# seven_segment_driver_sche2.net
KiCad netlist of a schematic drawn in Altium Designer
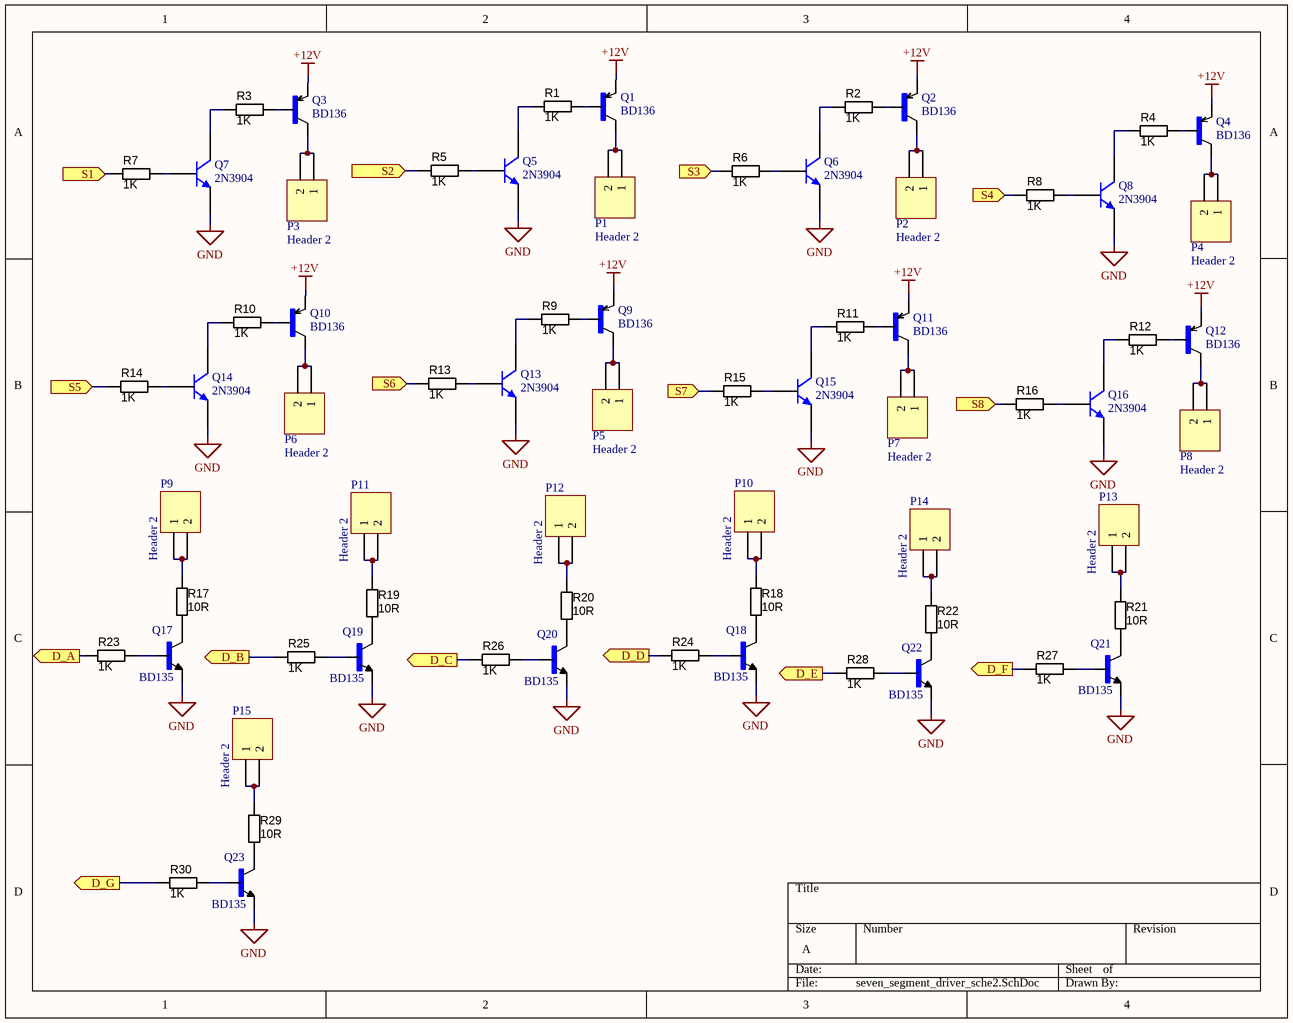
[diagram p0: seven_segment_driver_sche2.SchDoc]

(export (version "E")
  (design (tool "Eeschema 10.0.6"))
  (components
    (comp (ref "P1")
      (value "Header 2")
      (footprint "HDR1X2")
      (description "Header, 2-Pin")
      (fields (field (name "PUBLISHER") "Altium Limited"))
      (libsource (lib "Miscellaneous Connectors") (part "Header 2"))
    )
    (comp (ref "P2")
      (value "Header 2")
      (footprint "HDR1X2")
      (description "Header, 2-Pin")
      (fields (field (name "PUBLISHER") "Altium Limited"))
      (libsource (lib "Miscellaneous Connectors") (part "Header 2"))
    )
    (comp (ref "P3")
      (value "Header 2")
      (footprint "HDR1X2")
      (description "Header, 2-Pin")
      (fields (field (name "PUBLISHER") "Altium Limited"))
      (libsource (lib "Miscellaneous Connectors") (part "Header 2"))
    )
    (comp (ref "P4")
      (value "Header 2")
      (footprint "HDR1X2")
      (description "Header, 2-Pin")
      (fields (field (name "PUBLISHER") "Altium Limited"))
      (libsource (lib "Miscellaneous Connectors") (part "Header 2"))
    )
    (comp (ref "P5")
      (value "Header 2")
      (footprint "HDR1X2")
      (description "Header, 2-Pin")
      (fields (field (name "PUBLISHER") "Altium Limited"))
      (libsource (lib "Miscellaneous Connectors") (part "Header 2"))
    )
    (comp (ref "P6")
      (value "Header 2")
      (footprint "HDR1X2")
      (description "Header, 2-Pin")
      (fields (field (name "PUBLISHER") "Altium Limited"))
      (libsource (lib "Miscellaneous Connectors") (part "Header 2"))
    )
    (comp (ref "P7")
      (value "Header 2")
      (footprint "HDR1X2")
      (description "Header, 2-Pin")
      (fields (field (name "PUBLISHER") "Altium Limited"))
      (libsource (lib "Miscellaneous Connectors") (part "Header 2"))
    )
    (comp (ref "P8")
      (value "Header 2")
      (footprint "HDR1X2")
      (description "Header, 2-Pin")
      (fields (field (name "PUBLISHER") "Altium Limited"))
      (libsource (lib "Miscellaneous Connectors") (part "Header 2"))
    )
    (comp (ref "P9")
      (value "Header 2")
      (footprint "HDR1X2")
      (description "Header, 2-Pin")
      (fields (field (name "PUBLISHER") "Altium Limited"))
      (libsource (lib "") (part "Header 2_1"))
    )
    (comp (ref "P10")
      (value "Header 2")
      (footprint "HDR1X2")
      (description "Header, 2-Pin")
      (fields (field (name "PUBLISHER") "Altium Limited"))
      (libsource (lib "") (part "Header 2_1"))
    )
    (comp (ref "P11")
      (value "Header 2")
      (footprint "HDR1X2")
      (description "Header, 2-Pin")
      (fields (field (name "PUBLISHER") "Altium Limited"))
      (libsource (lib "") (part "Header 2_1"))
    )
    (comp (ref "P12")
      (value "Header 2")
      (footprint "HDR1X2")
      (description "Header, 2-Pin")
      (fields (field (name "PUBLISHER") "Altium Limited"))
      (libsource (lib "") (part "Header 2_1"))
    )
    (comp (ref "P13")
      (value "Header 2")
      (footprint "HDR1X2")
      (description "Header, 2-Pin")
      (fields (field (name "PUBLISHER") "Altium Limited"))
      (libsource (lib "") (part "Header 2_1"))
    )
    (comp (ref "P14")
      (value "Header 2")
      (footprint "HDR1X2")
      (description "Header, 2-Pin")
      (fields (field (name "PUBLISHER") "Altium Limited"))
      (libsource (lib "") (part "Header 2_1"))
    )
    (comp (ref "P15")
      (value "Header 2")
      (footprint "HDR1X2")
      (description "Header, 2-Pin")
      (fields (field (name "PUBLISHER") "Altium Limited"))
      (libsource (lib "") (part "Header 2_1"))
    )
    (comp (ref "Q1")
      (value "BD136")
      (footprint "*TO229P780X300X2000-3")
      (libsource (lib "") (part "BD136_1"))
    )
    (comp (ref "Q2")
      (value "BD136")
      (footprint "*TO229P780X300X2000-3")
      (libsource (lib "BD136") (part "BD136"))
    )
    (comp (ref "Q3")
      (value "BD136")
      (footprint "*TO229P780X300X2000-3")
      (libsource (lib "BD136") (part "BD136"))
    )
    (comp (ref "Q4")
      (value "BD136")
      (footprint "*TO229P780X300X2000-3")
      (libsource (lib "BD136") (part "BD136"))
    )
    (comp (ref "Q5")
      (value "2N3904")
      (footprint "TO-92_Flat")
      (description "NPN General Purpose Amplifier")
      (fields (field (name "PUBLISHER") "Altium Limited"))
      (libsource (lib "Miscellaneous Devices") (part "2N3904"))
    )
    (comp (ref "Q6")
      (value "2N3904")
      (footprint "TO-92_Flat")
      (description "NPN General Purpose Amplifier")
      (fields (field (name "PUBLISHER") "Altium Limited"))
      (libsource (lib "Miscellaneous Devices") (part "2N3904"))
    )
    (comp (ref "Q7")
      (value "2N3904")
      (footprint "TO-92_Flat")
      (description "NPN General Purpose Amplifier")
      (fields (field (name "PUBLISHER") "Altium Limited"))
      (libsource (lib "Miscellaneous Devices") (part "2N3904"))
    )
    (comp (ref "Q8")
      (value "2N3904")
      (footprint "TO-92_Flat")
      (description "NPN General Purpose Amplifier")
      (fields (field (name "PUBLISHER") "Altium Limited"))
      (libsource (lib "Miscellaneous Devices") (part "2N3904"))
    )
    (comp (ref "Q9")
      (value "BD136")
      (footprint "*TO229P780X300X2000-3")
      (libsource (lib "BD136") (part "BD136"))
    )
    (comp (ref "Q10")
      (value "BD136")
      (footprint "*TO229P780X300X2000-3")
      (libsource (lib "") (part "BD136_1"))
    )
    (comp (ref "Q11")
      (value "BD136")
      (footprint "*TO229P780X300X2000-3")
      (libsource (lib "BD136") (part "BD136"))
    )
    (comp (ref "Q12")
      (value "BD136")
      (footprint "*TO229P780X300X2000-3")
      (libsource (lib "BD136") (part "BD136"))
    )
    (comp (ref "Q13")
      (value "2N3904")
      (footprint "TO-92_Flat")
      (description "NPN General Purpose Amplifier")
      (fields (field (name "PUBLISHER") "Altium Limited"))
      (libsource (lib "Miscellaneous Devices") (part "2N3904"))
    )
    (comp (ref "Q14")
      (value "2N3904")
      (footprint "TO-92_Flat")
      (description "NPN General Purpose Amplifier")
      (fields (field (name "PUBLISHER") "Altium Limited"))
      (libsource (lib "Miscellaneous Devices") (part "2N3904"))
    )
    (comp (ref "Q15")
      (value "2N3904")
      (footprint "TO-92_Flat")
      (description "NPN General Purpose Amplifier")
      (fields (field (name "PUBLISHER") "Altium Limited"))
      (libsource (lib "Miscellaneous Devices") (part "2N3904"))
    )
    (comp (ref "Q16")
      (value "2N3904")
      (footprint "TO-92_Flat")
      (description "NPN General Purpose Amplifier")
      (fields (field (name "PUBLISHER") "Altium Limited"))
      (libsource (lib "Miscellaneous Devices") (part "2N3904"))
    )
    (comp (ref "Q17")
      (value "BD135")
      (footprint "*TO229P780X300X2000-3")
      (description "Trans GP BJT NPN 45V 1.5A 3-Pin TO-126")
      (fields (field (name "MF") "ON Semiconductor"))
      (libsource (lib "BD135") (part "BD135"))
    )
    (comp (ref "Q18")
      (value "BD135")
      (footprint "*TO229P780X300X2000-3")
      (description "Trans GP BJT NPN 45V 1.5A 3-Pin TO-126")
      (fields (field (name "MF") "ON Semiconductor"))
      (libsource (lib "BD135") (part "BD135"))
    )
    (comp (ref "Q19")
      (value "BD135")
      (footprint "*TO229P780X300X2000-3")
      (description "Trans GP BJT NPN 45V 1.5A 3-Pin TO-126")
      (fields (field (name "MF") "ON Semiconductor"))
      (libsource (lib "BD135") (part "BD135"))
    )
    (comp (ref "Q20")
      (value "BD135")
      (footprint "*TO229P780X300X2000-3")
      (description "Trans GP BJT NPN 45V 1.5A 3-Pin TO-126")
      (fields (field (name "MF") "ON Semiconductor"))
      (libsource (lib "BD135") (part "BD135"))
    )
    (comp (ref "Q21")
      (value "BD135")
      (footprint "*TO229P780X300X2000-3")
      (description "Trans GP BJT NPN 45V 1.5A 3-Pin TO-126")
      (fields (field (name "MF") "ON Semiconductor"))
      (libsource (lib "BD135") (part "BD135"))
    )
    (comp (ref "Q22")
      (value "BD135")
      (footprint "*TO229P780X300X2000-3")
      (description "Trans GP BJT NPN 45V 1.5A 3-Pin TO-126")
      (fields (field (name "MF") "ON Semiconductor"))
      (libsource (lib "BD135") (part "BD135"))
    )
    (comp (ref "Q23")
      (value "BD135")
      (footprint "*TO229P780X300X2000-3")
      (description "Trans GP BJT NPN 45V 1.5A 3-Pin TO-126")
      (fields (field (name "MF") "ON Semiconductor"))
      (libsource (lib "BD135") (part "BD135"))
    )
    (comp (ref "R1")
      (value "1K")
      (footprint "RESTH_AXIAL-0.4")
      (description "Resistor THD Axial 1k Ohm 0.25W 5% Carbon Film")
      (fields (field (name "TOLERANCE") "±5%") (field (name "Comment") "Carbon Film"))
      (libsource (lib "PBL - Resistors") (part "RES_1K_Axial_0.25W_5%"))
    )
    (comp (ref "R2")
      (value "1K")
      (footprint "RESTH_AXIAL-0.4")
      (description "Resistor THD Axial 1k Ohm 0.25W 5% Carbon Film")
      (fields (field (name "TOLERANCE") "±5%") (field (name "Comment") "Carbon Film"))
      (libsource (lib "PBL - Resistors") (part "RES_1K_Axial_0.25W_5%"))
    )
    (comp (ref "R3")
      (value "1K")
      (footprint "RESTH_AXIAL-0.4")
      (description "Resistor THD Axial 1k Ohm 0.25W 5% Carbon Film")
      (fields (field (name "TOLERANCE") "±5%") (field (name "Comment") "Carbon Film"))
      (libsource (lib "PBL - Resistors") (part "RES_1K_Axial_0.25W_5%"))
    )
    (comp (ref "R4")
      (value "1K")
      (footprint "RESTH_AXIAL-0.4")
      (description "Resistor THD Axial 1k Ohm 0.25W 5% Carbon Film")
      (fields (field (name "TOLERANCE") "±5%") (field (name "Comment") "Carbon Film"))
      (libsource (lib "PBL - Resistors") (part "RES_1K_Axial_0.25W_5%"))
    )
    (comp (ref "R5")
      (value "1K")
      (footprint "RESTH_AXIAL-0.4")
      (description "Resistor THD Axial 1k Ohm 0.25W 5% Carbon Film")
      (fields (field (name "TOLERANCE") "±5%") (field (name "Comment") "Carbon Film"))
      (libsource (lib "PBL - Resistors") (part "RES_1K_Axial_0.25W_5%"))
    )
    (comp (ref "R6")
      (value "1K")
      (footprint "RESTH_AXIAL-0.4")
      (description "Resistor THD Axial 1k Ohm 0.25W 5% Carbon Film")
      (fields (field (name "TOLERANCE") "±5%") (field (name "Comment") "Carbon Film"))
      (libsource (lib "PBL - Resistors") (part "RES_1K_Axial_0.25W_5%"))
    )
    (comp (ref "R7")
      (value "1K")
      (footprint "RESTH_AXIAL-0.4")
      (description "Resistor THD Axial 1k Ohm 0.25W 5% Carbon Film")
      (fields (field (name "TOLERANCE") "±5%") (field (name "Comment") "Carbon Film"))
      (libsource (lib "PBL - Resistors") (part "RES_1K_Axial_0.25W_5%"))
    )
    (comp (ref "R8")
      (value "1K")
      (footprint "RESTH_AXIAL-0.4")
      (description "Resistor THD Axial 1k Ohm 0.25W 5% Carbon Film")
      (fields (field (name "TOLERANCE") "±5%") (field (name "Comment") "Carbon Film"))
      (libsource (lib "PBL - Resistors") (part "RES_1K_Axial_0.25W_5%"))
    )
    (comp (ref "R9")
      (value "1K")
      (footprint "RESTH_AXIAL-0.4")
      (description "Resistor THD Axial 1k Ohm 0.25W 5% Carbon Film")
      (fields (field (name "TOLERANCE") "±5%") (field (name "Comment") "Carbon Film"))
      (libsource (lib "PBL - Resistors") (part "RES_1K_Axial_0.25W_5%"))
    )
    (comp (ref "R10")
      (value "1K")
      (footprint "RESTH_AXIAL-0.4")
      (description "Resistor THD Axial 1k Ohm 0.25W 5% Carbon Film")
      (fields (field (name "TOLERANCE") "±5%") (field (name "Comment") "Carbon Film"))
      (libsource (lib "PBL - Resistors") (part "RES_1K_Axial_0.25W_5%"))
    )
    (comp (ref "R11")
      (value "1K")
      (footprint "RESTH_AXIAL-0.4")
      (description "Resistor THD Axial 1k Ohm 0.25W 5% Carbon Film")
      (fields (field (name "TOLERANCE") "±5%") (field (name "Comment") "Carbon Film"))
      (libsource (lib "PBL - Resistors") (part "RES_1K_Axial_0.25W_5%"))
    )
    (comp (ref "R12")
      (value "1K")
      (footprint "RESTH_AXIAL-0.4")
      (description "Resistor THD Axial 1k Ohm 0.25W 5% Carbon Film")
      (fields (field (name "TOLERANCE") "±5%") (field (name "Comment") "Carbon Film"))
      (libsource (lib "PBL - Resistors") (part "RES_1K_Axial_0.25W_5%"))
    )
    (comp (ref "R13")
      (value "1K")
      (footprint "RESTH_AXIAL-0.4")
      (description "Resistor THD Axial 1k Ohm 0.25W 5% Carbon Film")
      (fields (field (name "TOLERANCE") "±5%") (field (name "Comment") "Carbon Film"))
      (libsource (lib "PBL - Resistors") (part "RES_1K_Axial_0.25W_5%"))
    )
    (comp (ref "R14")
      (value "1K")
      (footprint "RESTH_AXIAL-0.4")
      (description "Resistor THD Axial 1k Ohm 0.25W 5% Carbon Film")
      (fields (field (name "TOLERANCE") "±5%") (field (name "Comment") "Carbon Film"))
      (libsource (lib "PBL - Resistors") (part "RES_1K_Axial_0.25W_5%"))
    )
    (comp (ref "R15")
      (value "1K")
      (footprint "RESTH_AXIAL-0.4")
      (description "Resistor THD Axial 1k Ohm 0.25W 5% Carbon Film")
      (fields (field (name "TOLERANCE") "±5%") (field (name "Comment") "Carbon Film"))
      (libsource (lib "PBL - Resistors") (part "RES_1K_Axial_0.25W_5%"))
    )
    (comp (ref "R16")
      (value "1K")
      (footprint "RESTH_AXIAL-0.4")
      (description "Resistor THD Axial 1k Ohm 0.25W 5% Carbon Film")
      (fields (field (name "TOLERANCE") "±5%") (field (name "Comment") "Carbon Film"))
      (libsource (lib "PBL - Resistors") (part "RES_1K_Axial_0.25W_5%"))
    )
    (comp (ref "R17")
      (value "10R")
      (footprint "AXIAL-0.6")
      (description "Resistor THD 10 Ohm 1W 5% Metal Film")
      (fields (field (name "TOLERANCE") "±5%") (field (name "Comment") "Metal Film"))
      (libsource (lib "PBL - Resistors") (part "RES_10R_Axial_1W_5%"))
    )
    (comp (ref "R18")
      (value "10R")
      (footprint "AXIAL-0.6")
      (description "Resistor THD 10 Ohm 1W 5% Metal Film")
      (fields (field (name "TOLERANCE") "±5%") (field (name "Comment") "Metal Film"))
      (libsource (lib "PBL - Resistors") (part "RES_10R_Axial_1W_5%"))
    )
    (comp (ref "R19")
      (value "10R")
      (footprint "AXIAL-0.6")
      (description "Resistor THD 10 Ohm 1W 5% Metal Film")
      (fields (field (name "TOLERANCE") "±5%") (field (name "Comment") "Metal Film"))
      (libsource (lib "PBL - Resistors") (part "RES_10R_Axial_1W_5%"))
    )
    (comp (ref "R20")
      (value "10R")
      (footprint "AXIAL-0.6")
      (description "Resistor THD 10 Ohm 1W 5% Metal Film")
      (fields (field (name "TOLERANCE") "±5%") (field (name "Comment") "Metal Film"))
      (libsource (lib "PBL - Resistors") (part "RES_10R_Axial_1W_5%"))
    )
    (comp (ref "R21")
      (value "10R")
      (footprint "AXIAL-0.6")
      (description "Resistor THD 10 Ohm 1W 5% Metal Film")
      (fields (field (name "TOLERANCE") "±5%") (field (name "Comment") "Metal Film"))
      (libsource (lib "PBL - Resistors") (part "RES_10R_Axial_1W_5%"))
    )
    (comp (ref "R22")
      (value "10R")
      (footprint "AXIAL-0.6")
      (description "Resistor THD 10 Ohm 1W 5% Metal Film")
      (fields (field (name "TOLERANCE") "±5%") (field (name "Comment") "Metal Film"))
      (libsource (lib "PBL - Resistors") (part "RES_10R_Axial_1W_5%"))
    )
    (comp (ref "R23")
      (value "1K")
      (footprint "RESTH_AXIAL-0.4")
      (description "Resistor THD Axial 1k Ohm 0.25W 5% Carbon Film")
      (fields (field (name "TOLERANCE") "±5%") (field (name "Comment") "Carbon Film"))
      (libsource (lib "PBL - Resistors") (part "RES_1K_Axial_0.25W_5%"))
    )
    (comp (ref "R24")
      (value "1K")
      (footprint "RESTH_AXIAL-0.4")
      (description "Resistor THD Axial 1k Ohm 0.25W 5% Carbon Film")
      (fields (field (name "TOLERANCE") "±5%") (field (name "Comment") "Carbon Film"))
      (libsource (lib "PBL - Resistors") (part "RES_1K_Axial_0.25W_5%"))
    )
    (comp (ref "R25")
      (value "1K")
      (footprint "RESTH_AXIAL-0.4")
      (description "Resistor THD Axial 1k Ohm 0.25W 5% Carbon Film")
      (fields (field (name "TOLERANCE") "±5%") (field (name "Comment") "Carbon Film"))
      (libsource (lib "PBL - Resistors") (part "RES_1K_Axial_0.25W_5%"))
    )
    (comp (ref "R26")
      (value "1K")
      (footprint "RESTH_AXIAL-0.4")
      (description "Resistor THD Axial 1k Ohm 0.25W 5% Carbon Film")
      (fields (field (name "TOLERANCE") "±5%") (field (name "Comment") "Carbon Film"))
      (libsource (lib "PBL - Resistors") (part "RES_1K_Axial_0.25W_5%"))
    )
    (comp (ref "R27")
      (value "1K")
      (footprint "RESTH_AXIAL-0.4")
      (description "Resistor THD Axial 1k Ohm 0.25W 5% Carbon Film")
      (fields (field (name "TOLERANCE") "±5%") (field (name "Comment") "Carbon Film"))
      (libsource (lib "PBL - Resistors") (part "RES_1K_Axial_0.25W_5%"))
    )
    (comp (ref "R28")
      (value "1K")
      (footprint "RESTH_AXIAL-0.4")
      (description "Resistor THD Axial 1k Ohm 0.25W 5% Carbon Film")
      (fields (field (name "TOLERANCE") "±5%") (field (name "Comment") "Carbon Film"))
      (libsource (lib "PBL - Resistors") (part "RES_1K_Axial_0.25W_5%"))
    )
    (comp (ref "R29")
      (value "10R")
      (footprint "AXIAL-0.6")
      (description "Resistor THD 10 Ohm 1W 5% Metal Film")
      (fields (field (name "TOLERANCE") "±5%") (field (name "Comment") "Metal Film"))
      (libsource (lib "PBL - Resistors") (part "RES_10R_Axial_1W_5%"))
    )
    (comp (ref "R30")
      (value "1K")
      (footprint "RESTH_AXIAL-0.4")
      (description "Resistor THD Axial 1k Ohm 0.25W 5% Carbon Film")
      (fields (field (name "TOLERANCE") "±5%") (field (name "Comment") "Carbon Film"))
      (libsource (lib "PBL - Resistors") (part "RES_1K_Axial_0.25W_5%"))
    )
  )
  (nets
    (net (code "1") (name "+12V") (class "Default")
      (node (ref "Q1") (pin "1") (pinfunction "C_1") (pintype "passive"))
      (node (ref "Q10") (pin "1") (pinfunction "C_1") (pintype "passive"))
      (node (ref "Q11") (pin "1") (pinfunction "C_1") (pintype "passive"))
      (node (ref "Q12") (pin "1") (pinfunction "C_1") (pintype "passive"))
      (node (ref "Q2") (pin "1") (pinfunction "C_1") (pintype "passive"))
      (node (ref "Q3") (pin "1") (pinfunction "C_1") (pintype "passive"))
      (node (ref "Q4") (pin "1") (pinfunction "C_1") (pintype "passive"))
      (node (ref "Q9") (pin "1") (pinfunction "C_1") (pintype "passive"))
    )
    (net (code "2") (name "/D_A") (class "Default")
      (node (ref "R23") (pin "1") (pinfunction "1_1") (pintype "passive"))
    )
    (net (code "3") (name "/D_B") (class "Default")
      (node (ref "R25") (pin "1") (pinfunction "1_1") (pintype "passive"))
    )
    (net (code "4") (name "/D_C") (class "Default")
      (node (ref "R26") (pin "1") (pinfunction "1_1") (pintype "passive"))
    )
    (net (code "5") (name "/D_D") (class "Default")
      (node (ref "R24") (pin "1") (pinfunction "1_1") (pintype "passive"))
    )
    (net (code "6") (name "/D_E") (class "Default")
      (node (ref "R28") (pin "1") (pinfunction "1_1") (pintype "passive"))
    )
    (net (code "7") (name "/D_F") (class "Default")
      (node (ref "R27") (pin "1") (pinfunction "1_1") (pintype "passive"))
    )
    (net (code "8") (name "/D_G") (class "Default")
      (node (ref "R30") (pin "1") (pinfunction "1_1") (pintype "passive"))
    )
    (net (code "9") (name "/S1") (class "Default")
      (node (ref "R7") (pin "1") (pinfunction "1_1") (pintype "passive"))
    )
    (net (code "10") (name "/S2") (class "Default")
      (node (ref "R5") (pin "1") (pinfunction "1_1") (pintype "passive"))
    )
    (net (code "11") (name "/S3") (class "Default")
      (node (ref "R6") (pin "1") (pinfunction "1_1") (pintype "passive"))
    )
    (net (code "12") (name "/S4") (class "Default")
      (node (ref "R8") (pin "1") (pinfunction "1_1") (pintype "passive"))
    )
    (net (code "13") (name "/S5") (class "Default")
      (node (ref "R14") (pin "1") (pinfunction "1_1") (pintype "passive"))
    )
    (net (code "14") (name "/S6") (class "Default")
      (node (ref "R13") (pin "1") (pinfunction "1_1") (pintype "passive"))
    )
    (net (code "15") (name "/S7") (class "Default")
      (node (ref "R15") (pin "1") (pinfunction "1_1") (pintype "passive"))
    )
    (net (code "16") (name "/S8") (class "Default")
      (node (ref "R16") (pin "1") (pinfunction "1_1") (pintype "passive"))
    )
    (net (code "17") (name "GND") (class "Default")
      (node (ref "Q13") (pin "1") (pinfunction "E_1") (pintype "passive"))
      (node (ref "Q14") (pin "1") (pinfunction "E_1") (pintype "passive"))
      (node (ref "Q15") (pin "1") (pinfunction "E_1") (pintype "passive"))
      (node (ref "Q16") (pin "1") (pinfunction "E_1") (pintype "passive"))
      (node (ref "Q17") (pin "1") (pinfunction "E_1") (pintype "passive"))
      (node (ref "Q18") (pin "1") (pinfunction "E_1") (pintype "passive"))
      (node (ref "Q19") (pin "1") (pinfunction "E_1") (pintype "passive"))
      (node (ref "Q20") (pin "1") (pinfunction "E_1") (pintype "passive"))
      (node (ref "Q21") (pin "1") (pinfunction "E_1") (pintype "passive"))
      (node (ref "Q22") (pin "1") (pinfunction "E_1") (pintype "passive"))
      (node (ref "Q23") (pin "1") (pinfunction "E_1") (pintype "passive"))
      (node (ref "Q5") (pin "1") (pinfunction "E_1") (pintype "passive"))
      (node (ref "Q6") (pin "1") (pinfunction "E_1") (pintype "passive"))
      (node (ref "Q7") (pin "1") (pinfunction "E_1") (pintype "passive"))
      (node (ref "Q8") (pin "1") (pinfunction "E_1") (pintype "passive"))
    )
    (net (code "18") (name "Net-(P1-Pad1)") (class "Default")
      (node (ref "P1") (pin "1") (pinfunction "1_1") (pintype "passive"))
      (node (ref "P1") (pin "2") (pinfunction "2_2") (pintype "passive"))
      (node (ref "Q1") (pin "2") (pinfunction "C_2") (pintype "passive"))
    )
    (net (code "19") (name "Net-(P2-Pad1)") (class "Default")
      (node (ref "P2") (pin "1") (pinfunction "1_1") (pintype "passive"))
      (node (ref "P2") (pin "2") (pinfunction "2_2") (pintype "passive"))
      (node (ref "Q2") (pin "2") (pinfunction "C_2") (pintype "passive"))
    )
    (net (code "20") (name "Net-(P3-Pad1)") (class "Default")
      (node (ref "P3") (pin "1") (pinfunction "1_1") (pintype "passive"))
      (node (ref "P3") (pin "2") (pinfunction "2_2") (pintype "passive"))
      (node (ref "Q3") (pin "2") (pinfunction "C_2") (pintype "passive"))
    )
    (net (code "21") (name "Net-(P4-Pad1)") (class "Default")
      (node (ref "P4") (pin "1") (pinfunction "1_1") (pintype "passive"))
      (node (ref "P4") (pin "2") (pinfunction "2_2") (pintype "passive"))
      (node (ref "Q4") (pin "2") (pinfunction "C_2") (pintype "passive"))
    )
    (net (code "22") (name "Net-(P5-Pad1)") (class "Default")
      (node (ref "P5") (pin "1") (pinfunction "1_1") (pintype "passive"))
      (node (ref "P5") (pin "2") (pinfunction "2_2") (pintype "passive"))
      (node (ref "Q9") (pin "2") (pinfunction "C_2") (pintype "passive"))
    )
    (net (code "23") (name "Net-(P6-Pad1)") (class "Default")
      (node (ref "P6") (pin "1") (pinfunction "1_1") (pintype "passive"))
      (node (ref "P6") (pin "2") (pinfunction "2_2") (pintype "passive"))
      (node (ref "Q10") (pin "2") (pinfunction "C_2") (pintype "passive"))
    )
    (net (code "24") (name "Net-(P7-Pad1)") (class "Default")
      (node (ref "P7") (pin "1") (pinfunction "1_1") (pintype "passive"))
      (node (ref "P7") (pin "2") (pinfunction "2_2") (pintype "passive"))
      (node (ref "Q11") (pin "2") (pinfunction "C_2") (pintype "passive"))
    )
    (net (code "25") (name "Net-(P8-Pad1)") (class "Default")
      (node (ref "P8") (pin "1") (pinfunction "1_1") (pintype "passive"))
      (node (ref "P8") (pin "2") (pinfunction "2_2") (pintype "passive"))
      (node (ref "Q12") (pin "2") (pinfunction "C_2") (pintype "passive"))
    )
    (net (code "26") (name "Net-(P9-Pad1)") (class "Default")
      (node (ref "P9") (pin "1") (pinfunction "1_1") (pintype "passive"))
      (node (ref "P9") (pin "2") (pinfunction "2_2") (pintype "passive"))
      (node (ref "R17") (pin "1") (pinfunction "1_1") (pintype "passive"))
    )
    (net (code "27") (name "Net-(P10-Pad1)") (class "Default")
      (node (ref "P10") (pin "1") (pinfunction "1_1") (pintype "passive"))
      (node (ref "P10") (pin "2") (pinfunction "2_2") (pintype "passive"))
      (node (ref "R18") (pin "1") (pinfunction "1_1") (pintype "passive"))
    )
    (net (code "28") (name "Net-(P11-Pad1)") (class "Default")
      (node (ref "P11") (pin "1") (pinfunction "1_1") (pintype "passive"))
      (node (ref "P11") (pin "2") (pinfunction "2_2") (pintype "passive"))
      (node (ref "R19") (pin "1") (pinfunction "1_1") (pintype "passive"))
    )
    (net (code "29") (name "Net-(P12-Pad1)") (class "Default")
      (node (ref "P12") (pin "1") (pinfunction "1_1") (pintype "passive"))
      (node (ref "P12") (pin "2") (pinfunction "2_2") (pintype "passive"))
      (node (ref "R20") (pin "1") (pinfunction "1_1") (pintype "passive"))
    )
    (net (code "30") (name "Net-(P13-Pad1)") (class "Default")
      (node (ref "P13") (pin "1") (pinfunction "1_1") (pintype "passive"))
      (node (ref "P13") (pin "2") (pinfunction "2_2") (pintype "passive"))
      (node (ref "R21") (pin "1") (pinfunction "1_1") (pintype "passive"))
    )
    (net (code "31") (name "Net-(P14-Pad1)") (class "Default")
      (node (ref "P14") (pin "1") (pinfunction "1_1") (pintype "passive"))
      (node (ref "P14") (pin "2") (pinfunction "2_2") (pintype "passive"))
      (node (ref "R22") (pin "1") (pinfunction "1_1") (pintype "passive"))
    )
    (net (code "32") (name "Net-(P15-Pad1)") (class "Default")
      (node (ref "P15") (pin "1") (pinfunction "1_1") (pintype "passive"))
      (node (ref "P15") (pin "2") (pinfunction "2_2") (pintype "passive"))
      (node (ref "R29") (pin "1") (pinfunction "1_1") (pintype "passive"))
    )
    (net (code "33") (name "Net-(Q1-B)") (class "Default")
      (node (ref "Q1") (pin "3") (pinfunction "B_3") (pintype "passive"))
      (node (ref "R1") (pin "2") (pinfunction "2_2") (pintype "passive"))
    )
    (net (code "34") (name "Net-(Q2-B)") (class "Default")
      (node (ref "Q2") (pin "3") (pinfunction "B_3") (pintype "passive"))
      (node (ref "R2") (pin "2") (pinfunction "2_2") (pintype "passive"))
    )
    (net (code "35") (name "Net-(Q3-B)") (class "Default")
      (node (ref "Q3") (pin "3") (pinfunction "B_3") (pintype "passive"))
      (node (ref "R3") (pin "2") (pinfunction "2_2") (pintype "passive"))
    )
    (net (code "36") (name "Net-(Q4-B)") (class "Default")
      (node (ref "Q4") (pin "3") (pinfunction "B_3") (pintype "passive"))
      (node (ref "R4") (pin "2") (pinfunction "2_2") (pintype "passive"))
    )
    (net (code "37") (name "Net-(Q5-B)") (class "Default")
      (node (ref "Q5") (pin "2") (pinfunction "B_2") (pintype "passive"))
      (node (ref "R5") (pin "2") (pinfunction "2_2") (pintype "passive"))
    )
    (net (code "38") (name "Net-(Q5-C)") (class "Default")
      (node (ref "Q5") (pin "3") (pinfunction "C_3") (pintype "passive"))
      (node (ref "R1") (pin "1") (pinfunction "1_1") (pintype "passive"))
    )
    (net (code "39") (name "Net-(Q6-B)") (class "Default")
      (node (ref "Q6") (pin "2") (pinfunction "B_2") (pintype "passive"))
      (node (ref "R6") (pin "2") (pinfunction "2_2") (pintype "passive"))
    )
    (net (code "40") (name "Net-(Q6-C)") (class "Default")
      (node (ref "Q6") (pin "3") (pinfunction "C_3") (pintype "passive"))
      (node (ref "R2") (pin "1") (pinfunction "1_1") (pintype "passive"))
    )
    (net (code "41") (name "Net-(Q7-B)") (class "Default")
      (node (ref "Q7") (pin "2") (pinfunction "B_2") (pintype "passive"))
      (node (ref "R7") (pin "2") (pinfunction "2_2") (pintype "passive"))
    )
    (net (code "42") (name "Net-(Q7-C)") (class "Default")
      (node (ref "Q7") (pin "3") (pinfunction "C_3") (pintype "passive"))
      (node (ref "R3") (pin "1") (pinfunction "1_1") (pintype "passive"))
    )
    (net (code "43") (name "Net-(Q8-B)") (class "Default")
      (node (ref "Q8") (pin "2") (pinfunction "B_2") (pintype "passive"))
      (node (ref "R8") (pin "2") (pinfunction "2_2") (pintype "passive"))
    )
    (net (code "44") (name "Net-(Q8-C)") (class "Default")
      (node (ref "Q8") (pin "3") (pinfunction "C_3") (pintype "passive"))
      (node (ref "R4") (pin "1") (pinfunction "1_1") (pintype "passive"))
    )
    (net (code "45") (name "Net-(Q9-B)") (class "Default")
      (node (ref "Q9") (pin "3") (pinfunction "B_3") (pintype "passive"))
      (node (ref "R9") (pin "2") (pinfunction "2_2") (pintype "passive"))
    )
    (net (code "46") (name "Net-(Q10-B)") (class "Default")
      (node (ref "Q10") (pin "3") (pinfunction "B_3") (pintype "passive"))
      (node (ref "R10") (pin "2") (pinfunction "2_2") (pintype "passive"))
    )
    (net (code "47") (name "Net-(Q11-B)") (class "Default")
      (node (ref "Q11") (pin "3") (pinfunction "B_3") (pintype "passive"))
      (node (ref "R11") (pin "2") (pinfunction "2_2") (pintype "passive"))
    )
    (net (code "48") (name "Net-(Q12-B)") (class "Default")
      (node (ref "Q12") (pin "3") (pinfunction "B_3") (pintype "passive"))
      (node (ref "R12") (pin "2") (pinfunction "2_2") (pintype "passive"))
    )
    (net (code "49") (name "Net-(Q13-B)") (class "Default")
      (node (ref "Q13") (pin "2") (pinfunction "B_2") (pintype "passive"))
      (node (ref "R13") (pin "2") (pinfunction "2_2") (pintype "passive"))
    )
    (net (code "50") (name "Net-(Q13-C)") (class "Default")
      (node (ref "Q13") (pin "3") (pinfunction "C_3") (pintype "passive"))
      (node (ref "R9") (pin "1") (pinfunction "1_1") (pintype "passive"))
    )
    (net (code "51") (name "Net-(Q14-B)") (class "Default")
      (node (ref "Q14") (pin "2") (pinfunction "B_2") (pintype "passive"))
      (node (ref "R14") (pin "2") (pinfunction "2_2") (pintype "passive"))
    )
    (net (code "52") (name "Net-(Q14-C)") (class "Default")
      (node (ref "Q14") (pin "3") (pinfunction "C_3") (pintype "passive"))
      (node (ref "R10") (pin "1") (pinfunction "1_1") (pintype "passive"))
    )
    (net (code "53") (name "Net-(Q15-B)") (class "Default")
      (node (ref "Q15") (pin "2") (pinfunction "B_2") (pintype "passive"))
      (node (ref "R15") (pin "2") (pinfunction "2_2") (pintype "passive"))
    )
    (net (code "54") (name "Net-(Q15-C)") (class "Default")
      (node (ref "Q15") (pin "3") (pinfunction "C_3") (pintype "passive"))
      (node (ref "R11") (pin "1") (pinfunction "1_1") (pintype "passive"))
    )
    (net (code "55") (name "Net-(Q16-B)") (class "Default")
      (node (ref "Q16") (pin "2") (pinfunction "B_2") (pintype "passive"))
      (node (ref "R16") (pin "2") (pinfunction "2_2") (pintype "passive"))
    )
    (net (code "56") (name "Net-(Q16-C)") (class "Default")
      (node (ref "Q16") (pin "3") (pinfunction "C_3") (pintype "passive"))
      (node (ref "R12") (pin "1") (pinfunction "1_1") (pintype "passive"))
    )
    (net (code "57") (name "Net-(Q17-B)") (class "Default")
      (node (ref "Q17") (pin "3") (pinfunction "B_3") (pintype "passive"))
      (node (ref "R23") (pin "2") (pinfunction "2_2") (pintype "passive"))
    )
    (net (code "58") (name "Net-(Q17-C)") (class "Default")
      (node (ref "Q17") (pin "2") (pinfunction "C_2") (pintype "passive"))
      (node (ref "R17") (pin "2") (pinfunction "2_2") (pintype "passive"))
    )
    (net (code "59") (name "Net-(Q18-B)") (class "Default")
      (node (ref "Q18") (pin "3") (pinfunction "B_3") (pintype "passive"))
      (node (ref "R24") (pin "2") (pinfunction "2_2") (pintype "passive"))
    )
    (net (code "60") (name "Net-(Q18-C)") (class "Default")
      (node (ref "Q18") (pin "2") (pinfunction "C_2") (pintype "passive"))
      (node (ref "R18") (pin "2") (pinfunction "2_2") (pintype "passive"))
    )
    (net (code "61") (name "Net-(Q19-B)") (class "Default")
      (node (ref "Q19") (pin "3") (pinfunction "B_3") (pintype "passive"))
      (node (ref "R25") (pin "2") (pinfunction "2_2") (pintype "passive"))
    )
    (net (code "62") (name "Net-(Q19-C)") (class "Default")
      (node (ref "Q19") (pin "2") (pinfunction "C_2") (pintype "passive"))
      (node (ref "R19") (pin "2") (pinfunction "2_2") (pintype "passive"))
    )
    (net (code "63") (name "Net-(Q20-B)") (class "Default")
      (node (ref "Q20") (pin "3") (pinfunction "B_3") (pintype "passive"))
      (node (ref "R26") (pin "2") (pinfunction "2_2") (pintype "passive"))
    )
    (net (code "64") (name "Net-(Q20-C)") (class "Default")
      (node (ref "Q20") (pin "2") (pinfunction "C_2") (pintype "passive"))
      (node (ref "R20") (pin "2") (pinfunction "2_2") (pintype "passive"))
    )
    (net (code "65") (name "Net-(Q21-B)") (class "Default")
      (node (ref "Q21") (pin "3") (pinfunction "B_3") (pintype "passive"))
      (node (ref "R27") (pin "2") (pinfunction "2_2") (pintype "passive"))
    )
    (net (code "66") (name "Net-(Q21-C)") (class "Default")
      (node (ref "Q21") (pin "2") (pinfunction "C_2") (pintype "passive"))
      (node (ref "R21") (pin "2") (pinfunction "2_2") (pintype "passive"))
    )
    (net (code "67") (name "Net-(Q22-B)") (class "Default")
      (node (ref "Q22") (pin "3") (pinfunction "B_3") (pintype "passive"))
      (node (ref "R28") (pin "2") (pinfunction "2_2") (pintype "passive"))
    )
    (net (code "68") (name "Net-(Q22-C)") (class "Default")
      (node (ref "Q22") (pin "2") (pinfunction "C_2") (pintype "passive"))
      (node (ref "R22") (pin "2") (pinfunction "2_2") (pintype "passive"))
    )
    (net (code "69") (name "Net-(Q23-B)") (class "Default")
      (node (ref "Q23") (pin "3") (pinfunction "B_3") (pintype "passive"))
      (node (ref "R30") (pin "2") (pinfunction "2_2") (pintype "passive"))
    )
    (net (code "70") (name "Net-(Q23-C)") (class "Default")
      (node (ref "Q23") (pin "2") (pinfunction "C_2") (pintype "passive"))
      (node (ref "R29") (pin "2") (pinfunction "2_2") (pintype "passive"))
    )
  )
)
